# SimpleFOC.net
KiCad netlist of a schematic drawn in Altium Designer
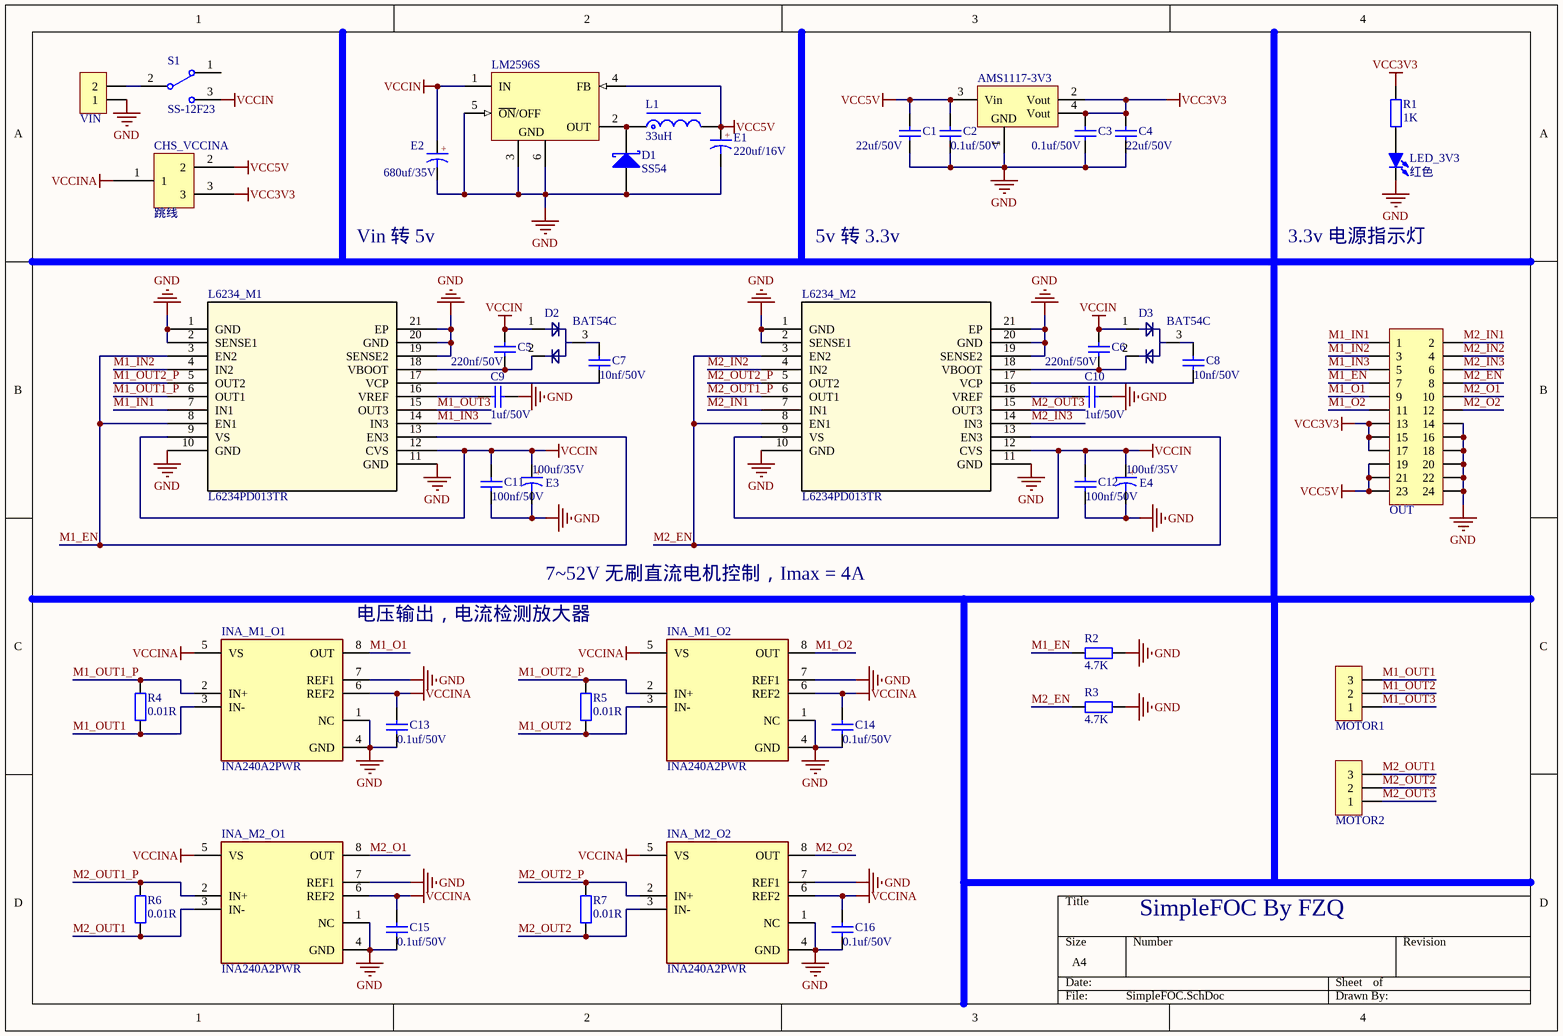
[diagram p0: SimpleFOC.SchDoc]

(export (version "E")
  (design (tool "Eeschema 10.0.6"))
  (components
    (comp (ref "AMS1117-3V3")
      (value "AMS1117-3V3")
      (footprint "SOT223_L")
      (description "三端稳压芯片")
      (libsource (lib "1.1 - 电源类芯片") (part "AMS1117"))
    )
    (comp (ref "C1")
      (value "22uf/50V")
      (footprint "C0603_L")
      (description "贴片电容")
      (libsource (lib "0.1 - 电阻-电容-电感-电位器") (part "C"))
    )
    (comp (ref "C2")
      (value "0.1uf/50V")
      (footprint "C0603_L")
      (description "贴片电容")
      (libsource (lib "0.1 - 电阻-电容-电感-电位器") (part "C"))
    )
    (comp (ref "C3")
      (value "0.1uf/50V")
      (footprint "C0603_L")
      (description "贴片电容")
      (libsource (lib "0.1 - 电阻-电容-电感-电位器") (part "C"))
    )
    (comp (ref "C4")
      (value "22uf/50V")
      (footprint "C0603_L")
      (description "贴片电容")
      (libsource (lib "0.1 - 电阻-电容-电感-电位器") (part "C"))
    )
    (comp (ref "C5")
      (value "220nf/50V")
      (footprint "C0603_L")
      (description "贴片电容")
      (libsource (lib "0.1 - 电阻-电容-电感-电位器") (part "C"))
    )
    (comp (ref "C6")
      (value "220nf/50V")
      (footprint "C0603_L")
      (description "贴片电容")
      (libsource (lib "0.1 - 电阻-电容-电感-电位器") (part "C"))
    )
    (comp (ref "C7")
      (value "10nf/50V")
      (footprint "C0603_L")
      (description "贴片电容")
      (libsource (lib "0.1 - 电阻-电容-电感-电位器") (part "C"))
    )
    (comp (ref "C8")
      (value "10nf/50V")
      (footprint "C0603_L")
      (description "贴片电容")
      (libsource (lib "0.1 - 电阻-电容-电感-电位器") (part "C"))
    )
    (comp (ref "C9")
      (value "1uf/50V")
      (footprint "C0603_L")
      (description "贴片电容")
      (libsource (lib "0.1 - 电阻-电容-电感-电位器") (part "C"))
    )
    (comp (ref "C10")
      (value "1uf/50V")
      (footprint "C0603_L")
      (description "贴片电容")
      (libsource (lib "0.1 - 电阻-电容-电感-电位器") (part "C"))
    )
    (comp (ref "C11")
      (value "100nf/50V")
      (footprint "C0603_L")
      (description "贴片电容")
      (libsource (lib "0.1 - 电阻-电容-电感-电位器") (part "C"))
    )
    (comp (ref "C12")
      (value "100nf/50V")
      (footprint "C0603_L")
      (description "贴片电容")
      (libsource (lib "0.1 - 电阻-电容-电感-电位器") (part "C"))
    )
    (comp (ref "C13")
      (value "0.1uf/50V")
      (footprint "C0603_L")
      (description "贴片电容")
      (libsource (lib "0.1 - 电阻-电容-电感-电位器") (part "C"))
    )
    (comp (ref "C14")
      (value "0.1uf/50V")
      (footprint "C0603_L")
      (description "贴片电容")
      (libsource (lib "0.1 - 电阻-电容-电感-电位器") (part "C"))
    )
    (comp (ref "C15")
      (value "0.1uf/50V")
      (footprint "C0603_L")
      (description "贴片电容")
      (libsource (lib "0.1 - 电阻-电容-电感-电位器") (part "C"))
    )
    (comp (ref "C16")
      (value "0.1uf/50V")
      (footprint "C0603_L")
      (description "贴片电容")
      (libsource (lib "0.1 - 电阻-电容-电感-电位器") (part "C"))
    )
    (comp (ref "CHS_VCCINA") (value "跳线") (footprint "0603") (libsource (lib "SimpleFOC") (part "跳线")))
    (comp (ref "D1")
      (value "SS54")
      (footprint "SMA")
      (description "肖特基二极管(5A/40V)")
      (libsource (lib "0.2 - 二极管-TVS-整流桥") (part "SS14"))
    )
    (comp (ref "D2")
      (value "BAT54C")
      (footprint "SOT23-3N")
      (description "两路肖特基二极管")
      (libsource (lib "SimpleFOC") (part "LBAT54SLT1G"))
    )
    (comp (ref "D3")
      (value "BAT54C")
      (footprint "SOT23-3N")
      (description "两路肖特基二极管")
      (libsource (lib "SimpleFOC") (part "LBAT54SLT1G"))
    )
    (comp (ref "E1")
      (value "220uf/16V")
      (footprint "CE D(6.3*7.7)")
      (description "贴片电解电容")
      (libsource (lib "0.1 - 电阻-电容-电感-电位器") (part "CE_SMD"))
    )
    (comp (ref "E2")
      (value "680uf/35V")
      (footprint "CE G(12.5*13.5)")
      (description "贴片电解电容")
      (libsource (lib "0.1 - 电阻-电容-电感-电位器") (part "CE_SMD"))
    )
    (comp (ref "E3")
      (value "100uf/35V")
      (footprint "CE D(6.3*7.7)")
      (description "贴片电解电容")
      (libsource (lib "0.1 - 电阻-电容-电感-电位器") (part "CE_SMD"))
    )
    (comp (ref "E4")
      (value "100uf/35V")
      (footprint "CE D(6.3*7.7)")
      (description "贴片电解电容")
      (libsource (lib "0.1 - 电阻-电容-电感-电位器") (part "CE_SMD"))
    )
    (comp (ref "INA_M1_O1")
      (value "INA240A2PWR")
      (footprint "INA240A2PWR")
      (description "IC AMP CURRENT SENSE 8-TSSOP")
      (fields
        (field (name "OCTOPART") "https://octopart.com/ina240a2pwr-texas+instruments-75431049")
        (field (name "MANUFACTURER") "Texas Instruments")
      )
      (libsource (lib "SimpleFOC") (part "INA240A2PWR"))
    )
    (comp (ref "INA_M1_O2")
      (value "INA240A2PWR")
      (footprint "INA240A2PWR")
      (description "IC AMP CURRENT SENSE 8-TSSOP")
      (fields
        (field (name "OCTOPART") "https://octopart.com/ina240a2pwr-texas+instruments-75431049")
        (field (name "MANUFACTURER") "Texas Instruments")
      )
      (libsource (lib "SimpleFOC") (part "INA240A2PWR"))
    )
    (comp (ref "INA_M2_O1")
      (value "INA240A2PWR")
      (footprint "INA240A2PWR")
      (description "IC AMP CURRENT SENSE 8-TSSOP")
      (fields
        (field (name "OCTOPART") "https://octopart.com/ina240a2pwr-texas+instruments-75431049")
        (field (name "MANUFACTURER") "Texas Instruments")
      )
      (libsource (lib "SimpleFOC") (part "INA240A2PWR"))
    )
    (comp (ref "INA_M2_O2")
      (value "INA240A2PWR")
      (footprint "INA240A2PWR")
      (description "IC AMP CURRENT SENSE 8-TSSOP")
      (fields
        (field (name "OCTOPART") "https://octopart.com/ina240a2pwr-texas+instruments-75431049")
        (field (name "MANUFACTURER") "Texas Instruments")
      )
      (libsource (lib "SimpleFOC") (part "INA240A2PWR"))
    )
    (comp (ref "L1")
      (value "33uH")
      (footprint "CDRH74")
      (description "CDRH功率屏蔽电感")
      (libsource (lib "0.1 - 电阻-电容-电感-电位器") (part "L-CDRH"))
    )
    (comp (ref "L6234_M1")
      (value "L6234PD013TR")
      (footprint "SOIC127P1420X360-21N")
      (description "No Description Available")
      (fields (field (name "COPYRIGHT") "Copyright (C) 2021 Accelerated Designs. All rights reserved"))
      (libsource (lib "SimpleFOC") (part "L6234PD013TR"))
    )
    (comp (ref "L6234_M2")
      (value "L6234PD013TR")
      (footprint "SOIC127P1420X360-21N")
      (description "No Description Available")
      (fields (field (name "COPYRIGHT") "Copyright (C) 2021 Accelerated Designs. All rights reserved"))
      (libsource (lib "SimpleFOC") (part "L6234PD013TR"))
    )
    (comp (ref "LED_3V3")
      (value "红色")
      (footprint "LED0603_R")
      (description "贴片LED")
      (libsource (lib "0.3 - LED发光二极管") (part "LED-SMD"))
    )
    (comp (ref "LM2596S")
      (value "LM2596S")
      (footprint "TO263-5A")
      (description "3A DC-DC降压芯片")
      (libsource (lib "1.1 - 电源类芯片") (part "LM2596S"))
    )
    (comp (ref "MOTOR1")
      (value "HDR-1X3")
      (footprint "KF301-5.0-3P")
      (description "3P接插件")
      (libsource (lib "6.0 - 接插件-脚距5.0") (part "Header 3"))
    )
    (comp (ref "MOTOR2")
      (value "HDR-1X3")
      (footprint "KF301-5.0-3P")
      (description "3P接插件")
      (libsource (lib "6.0 - 接插件-脚距5.0") (part "Header 3"))
    )
    (comp (ref "OUT")
      (value "Header 2X11")
      (footprint "HDR2.54-LI-2x12P")
      (description "12*2P接插件")
      (libsource (lib "5.4 - 接插件-脚距2.54 (100mil) ") (part "Header 12X2"))
    )
    (comp (ref "R1")
      (value "1K")
      (footprint "R0603_L")
      (description "贴片电阻")
      (libsource (lib "0.1 - 电阻-电容-电感-电位器") (part "R"))
    )
    (comp (ref "R2")
      (value "4.7K")
      (footprint "R0603_L")
      (description "贴片电阻")
      (libsource (lib "0.1 - 电阻-电容-电感-电位器") (part "R"))
    )
    (comp (ref "R3")
      (value "4.7K")
      (footprint "R0603_L")
      (description "贴片电阻")
      (libsource (lib "0.1 - 电阻-电容-电感-电位器") (part "R"))
    )
    (comp (ref "R4")
      (value "0.01R")
      (footprint "R0805_L")
      (description "贴片电阻")
      (libsource (lib "0.1 - 电阻-电容-电感-电位器") (part "R"))
    )
    (comp (ref "R5")
      (value "0.01R")
      (footprint "R0805_L")
      (description "贴片电阻")
      (libsource (lib "0.1 - 电阻-电容-电感-电位器") (part "R"))
    )
    (comp (ref "R6")
      (value "0.01R")
      (footprint "R0805_L")
      (description "贴片电阻")
      (libsource (lib "0.1 - 电阻-电容-电感-电位器") (part "R"))
    )
    (comp (ref "R7")
      (value "0.01R")
      (footprint "R0805_L")
      (description "贴片电阻")
      (libsource (lib "0.1 - 电阻-电容-电感-电位器") (part "R"))
    )
    (comp (ref "S1")
      (value "SS-12F23")
      (footprint "SS-12D10")
      (description "1路波动开关")
      (libsource (lib "0.7 - 常用按键-开关-蜂鸣器-电池-测试点") (part "SSW-1P"))
    )
    (comp (ref "VIN")
      (value "HDR-1X2")
      (footprint "KF301-5.0-2P")
      (description "2P接插件")
      (libsource (lib "6.0 - 接插件-脚距5.0") (part "Header 2"))
    )
  )
  (nets
    (net (code "1") (name "/M1_EN") (class "Default")
      (node (ref "L6234_M1") (pin "13") (pinfunction "EN3_13") (pintype "passive"))
      (node (ref "L6234_M1") (pin "3") (pinfunction "EN2_3") (pintype "passive"))
      (node (ref "L6234_M1") (pin "8") (pinfunction "EN1_8") (pintype "passive"))
      (node (ref "OUT") (pin "7") (pinfunction "7_7") (pintype "passive"))
      (node (ref "R2") (pin "1") (pinfunction "1_1") (pintype "passive"))
    )
    (net (code "2") (name "/M1_IN1") (class "Default")
      (node (ref "L6234_M1") (pin "7") (pinfunction "IN1_7") (pintype "passive"))
      (node (ref "OUT") (pin "1") (pinfunction "1_1") (pintype "passive"))
    )
    (net (code "3") (name "/M1_IN2") (class "Default")
      (node (ref "L6234_M1") (pin "4") (pinfunction "IN2_4") (pintype "passive"))
      (node (ref "OUT") (pin "3") (pinfunction "3_3") (pintype "passive"))
    )
    (net (code "4") (name "/M1_IN3") (class "Default")
      (node (ref "L6234_M1") (pin "14") (pinfunction "IN3_14") (pintype "passive"))
      (node (ref "OUT") (pin "5") (pinfunction "5_5") (pintype "passive"))
    )
    (net (code "5") (name "/M1_O1") (class "Default")
      (node (ref "INA_M1_O1") (pin "8") (pinfunction "OUT_8") (pintype "passive"))
      (node (ref "OUT") (pin "9") (pinfunction "9_9") (pintype "passive"))
    )
    (net (code "6") (name "/M1_O2") (class "Default")
      (node (ref "INA_M1_O2") (pin "8") (pinfunction "OUT_8") (pintype "passive"))
      (node (ref "OUT") (pin "11") (pinfunction "11_11") (pintype "passive"))
    )
    (net (code "7") (name "/M1_OUT1") (class "Default")
      (node (ref "INA_M1_O1") (pin "3") (pinfunction "IN-_3") (pintype "tri_state"))
      (node (ref "MOTOR1") (pin "3") (pinfunction "3_3") (pintype "passive"))
      (node (ref "R4") (pin "2") (pinfunction "2_2") (pintype "passive"))
    )
    (net (code "8") (name "/M1_OUT1_P") (class "Default")
      (node (ref "INA_M1_O1") (pin "2") (pinfunction "IN+_2") (pintype "tri_state"))
      (node (ref "L6234_M1") (pin "6") (pinfunction "OUT1_6") (pintype "passive"))
      (node (ref "R4") (pin "1") (pinfunction "1_1") (pintype "passive"))
    )
    (net (code "9") (name "/M1_OUT2") (class "Default")
      (node (ref "INA_M1_O2") (pin "3") (pinfunction "IN-_3") (pintype "tri_state"))
      (node (ref "MOTOR1") (pin "2") (pinfunction "2_2") (pintype "passive"))
      (node (ref "R5") (pin "2") (pinfunction "2_2") (pintype "passive"))
    )
    (net (code "10") (name "/M1_OUT2_P") (class "Default")
      (node (ref "INA_M1_O2") (pin "2") (pinfunction "IN+_2") (pintype "tri_state"))
      (node (ref "L6234_M1") (pin "5") (pinfunction "OUT2_5") (pintype "passive"))
      (node (ref "R5") (pin "1") (pinfunction "1_1") (pintype "passive"))
    )
    (net (code "11") (name "/M1_OUT3") (class "Default")
      (node (ref "L6234_M1") (pin "15") (pinfunction "OUT3_15") (pintype "passive"))
      (node (ref "MOTOR1") (pin "1") (pinfunction "1_1") (pintype "passive"))
    )
    (net (code "12") (name "/M2_EN") (class "Default")
      (node (ref "L6234_M2") (pin "13") (pinfunction "EN3_13") (pintype "passive"))
      (node (ref "L6234_M2") (pin "3") (pinfunction "EN2_3") (pintype "passive"))
      (node (ref "L6234_M2") (pin "8") (pinfunction "EN1_8") (pintype "passive"))
      (node (ref "OUT") (pin "8") (pinfunction "8_8") (pintype "passive"))
      (node (ref "R3") (pin "1") (pinfunction "1_1") (pintype "passive"))
    )
    (net (code "13") (name "/M2_IN1") (class "Default")
      (node (ref "L6234_M2") (pin "7") (pinfunction "IN1_7") (pintype "passive"))
      (node (ref "OUT") (pin "2") (pinfunction "2_2") (pintype "passive"))
    )
    (net (code "14") (name "/M2_IN2") (class "Default")
      (node (ref "L6234_M2") (pin "4") (pinfunction "IN2_4") (pintype "passive"))
      (node (ref "OUT") (pin "4") (pinfunction "4_4") (pintype "passive"))
    )
    (net (code "15") (name "/M2_IN3") (class "Default")
      (node (ref "L6234_M2") (pin "14") (pinfunction "IN3_14") (pintype "passive"))
      (node (ref "OUT") (pin "6") (pinfunction "6_6") (pintype "passive"))
    )
    (net (code "16") (name "/M2_O1") (class "Default")
      (node (ref "INA_M2_O1") (pin "8") (pinfunction "OUT_8") (pintype "passive"))
      (node (ref "OUT") (pin "10") (pinfunction "10_10") (pintype "passive"))
    )
    (net (code "17") (name "/M2_O2") (class "Default")
      (node (ref "INA_M2_O2") (pin "8") (pinfunction "OUT_8") (pintype "passive"))
      (node (ref "OUT") (pin "12") (pinfunction "12_12") (pintype "passive"))
    )
    (net (code "18") (name "/M2_OUT1") (class "Default")
      (node (ref "INA_M2_O1") (pin "3") (pinfunction "IN-_3") (pintype "tri_state"))
      (node (ref "MOTOR2") (pin "3") (pinfunction "3_3") (pintype "passive"))
      (node (ref "R6") (pin "2") (pinfunction "2_2") (pintype "passive"))
    )
    (net (code "19") (name "/M2_OUT1_P") (class "Default")
      (node (ref "INA_M2_O1") (pin "2") (pinfunction "IN+_2") (pintype "tri_state"))
      (node (ref "L6234_M2") (pin "6") (pinfunction "OUT1_6") (pintype "passive"))
      (node (ref "R6") (pin "1") (pinfunction "1_1") (pintype "passive"))
    )
    (net (code "20") (name "/M2_OUT2") (class "Default")
      (node (ref "INA_M2_O2") (pin "3") (pinfunction "IN-_3") (pintype "tri_state"))
      (node (ref "MOTOR2") (pin "2") (pinfunction "2_2") (pintype "passive"))
      (node (ref "R7") (pin "2") (pinfunction "2_2") (pintype "passive"))
    )
    (net (code "21") (name "/M2_OUT2_P") (class "Default")
      (node (ref "INA_M2_O2") (pin "2") (pinfunction "IN+_2") (pintype "tri_state"))
      (node (ref "L6234_M2") (pin "5") (pinfunction "OUT2_5") (pintype "passive"))
      (node (ref "R7") (pin "1") (pinfunction "1_1") (pintype "passive"))
    )
    (net (code "22") (name "/M2_OUT3") (class "Default")
      (node (ref "L6234_M2") (pin "15") (pinfunction "OUT3_15") (pintype "passive"))
      (node (ref "MOTOR2") (pin "1") (pinfunction "1_1") (pintype "passive"))
    )
    (net (code "23") (name "GND") (class "Default")
      (node (ref "AMS1117-3V3") (pin "1") (pinfunction "GND_1") (pintype "passive"))
      (node (ref "C1") (pin "1") (pinfunction "1_1") (pintype "passive"))
      (node (ref "C10") (pin "1") (pinfunction "1_1") (pintype "passive"))
      (node (ref "C11") (pin "1") (pinfunction "1_1") (pintype "passive"))
      (node (ref "C12") (pin "1") (pinfunction "1_1") (pintype "passive"))
      (node (ref "C13") (pin "1") (pinfunction "1_1") (pintype "passive"))
      (node (ref "C14") (pin "1") (pinfunction "1_1") (pintype "passive"))
      (node (ref "C15") (pin "1") (pinfunction "1_1") (pintype "passive"))
      (node (ref "C16") (pin "1") (pinfunction "1_1") (pintype "passive"))
      (node (ref "C2") (pin "1") (pinfunction "1_1") (pintype "passive"))
      (node (ref "C3") (pin "1") (pinfunction "1_1") (pintype "passive"))
      (node (ref "C4") (pin "1") (pinfunction "1_1") (pintype "passive"))
      (node (ref "C9") (pin "1") (pinfunction "1_1") (pintype "passive"))
      (node (ref "D1") (pin "1") (pinfunction "A_1") (pintype "passive"))
      (node (ref "E1") (pin "2") (pinfunction "2_2") (pintype "passive"))
      (node (ref "E2") (pin "2") (pinfunction "2_2") (pintype "passive"))
      (node (ref "E3") (pin "2") (pinfunction "2_2") (pintype "passive"))
      (node (ref "E4") (pin "2") (pinfunction "2_2") (pintype "passive"))
      (node (ref "INA_M1_O1") (pin "1") (pinfunction "NC_1") (pintype "passive"))
      (node (ref "INA_M1_O1") (pin "4") (pinfunction "GND_4") (pintype "power_in"))
      (node (ref "INA_M1_O1") (pin "7") (pinfunction "REF1_7") (pintype "passive"))
      (node (ref "INA_M1_O2") (pin "1") (pinfunction "NC_1") (pintype "passive"))
      (node (ref "INA_M1_O2") (pin "4") (pinfunction "GND_4") (pintype "power_in"))
      (node (ref "INA_M1_O2") (pin "7") (pinfunction "REF1_7") (pintype "passive"))
      (node (ref "INA_M2_O1") (pin "1") (pinfunction "NC_1") (pintype "passive"))
      (node (ref "INA_M2_O1") (pin "4") (pinfunction "GND_4") (pintype "power_in"))
      (node (ref "INA_M2_O1") (pin "7") (pinfunction "REF1_7") (pintype "passive"))
      (node (ref "INA_M2_O2") (pin "1") (pinfunction "NC_1") (pintype "passive"))
      (node (ref "INA_M2_O2") (pin "4") (pinfunction "GND_4") (pintype "power_in"))
      (node (ref "INA_M2_O2") (pin "7") (pinfunction "REF1_7") (pintype "passive"))
      (node (ref "L6234_M1") (pin "1") (pinfunction "GND_1") (pintype "power_in"))
      (node (ref "L6234_M1") (pin "10") (pinfunction "GND_10") (pintype "power_in"))
      (node (ref "L6234_M1") (pin "11") (pinfunction "GND_11") (pintype "power_in"))
      (node (ref "L6234_M1") (pin "19") (pinfunction "SENSE2_19") (pintype "passive"))
      (node (ref "L6234_M1") (pin "2") (pinfunction "SENSE1_2") (pintype "passive"))
      (node (ref "L6234_M1") (pin "20") (pinfunction "GND_20") (pintype "power_in"))
      (node (ref "L6234_M1") (pin "21") (pinfunction "EP_21") (pintype "passive"))
      (node (ref "L6234_M2") (pin "1") (pinfunction "GND_1") (pintype "power_in"))
      (node (ref "L6234_M2") (pin "10") (pinfunction "GND_10") (pintype "power_in"))
      (node (ref "L6234_M2") (pin "11") (pinfunction "GND_11") (pintype "power_in"))
      (node (ref "L6234_M2") (pin "19") (pinfunction "SENSE2_19") (pintype "passive"))
      (node (ref "L6234_M2") (pin "2") (pinfunction "SENSE1_2") (pintype "passive"))
      (node (ref "L6234_M2") (pin "20") (pinfunction "GND_20") (pintype "power_in"))
      (node (ref "L6234_M2") (pin "21") (pinfunction "EP_21") (pintype "passive"))
      (node (ref "LED_3V3") (pin "2") (pinfunction "K_2") (pintype "passive"))
      (node (ref "LM2596S") (pin "3") (pinfunction "GND_3") (pintype "power_in"))
      (node (ref "LM2596S") (pin "5") (pinfunction "~{ON}/OFF_5") (pintype "input"))
      (node (ref "LM2596S") (pin "6") (pinfunction "GND_6") (pintype "power_in"))
      (node (ref "OUT") (pin "14") (pinfunction "14_14") (pintype "passive"))
      (node (ref "OUT") (pin "16") (pinfunction "16_16") (pintype "passive"))
      (node (ref "OUT") (pin "18") (pinfunction "18_18") (pintype "passive"))
      (node (ref "OUT") (pin "20") (pinfunction "20_20") (pintype "passive"))
      (node (ref "OUT") (pin "22") (pinfunction "22_22") (pintype "passive"))
      (node (ref "OUT") (pin "24") (pinfunction "24_24") (pintype "passive"))
      (node (ref "R2") (pin "2") (pinfunction "2_2") (pintype "passive"))
      (node (ref "R3") (pin "2") (pinfunction "2_2") (pintype "passive"))
      (node (ref "VIN") (pin "1") (pinfunction "1_1") (pintype "passive"))
    )
    (net (code "24") (name "Net-(C7-Pad2)") (class "Default")
      (node (ref "C7") (pin "2") (pinfunction "2_2") (pintype "passive"))
      (node (ref "D2") (pin "3") (pinfunction "3_3") (pintype "passive"))
    )
    (net (code "25") (name "Net-(C8-Pad2)") (class "Default")
      (node (ref "C8") (pin "2") (pinfunction "2_2") (pintype "passive"))
      (node (ref "D3") (pin "3") (pinfunction "3_3") (pintype "passive"))
    )
    (net (code "26") (name "Net-(D1-K)") (class "Default")
      (node (ref "D1") (pin "2") (pinfunction "K_2") (pintype "passive"))
      (node (ref "L1") (pin "1") (pinfunction "1_1") (pintype "passive"))
      (node (ref "LM2596S") (pin "2") (pinfunction "OUT_2") (pintype "power_in"))
    )
    (net (code "27") (name "Net-(L6234_M1-VBOOT)") (class "Default")
      (node (ref "C5") (pin "1") (pinfunction "1_1") (pintype "passive"))
      (node (ref "D2") (pin "2") (pinfunction "2_2") (pintype "passive"))
      (node (ref "L6234_M1") (pin "18") (pinfunction "VBOOT_18") (pintype "power_in"))
    )
    (net (code "28") (name "Net-(L6234_M1-VCP)") (class "Default")
      (node (ref "C7") (pin "1") (pinfunction "1_1") (pintype "passive"))
      (node (ref "L6234_M1") (pin "17") (pinfunction "VCP_17") (pintype "power_in"))
    )
    (net (code "29") (name "Net-(L6234_M1-VREF)") (class "Default")
      (node (ref "C9") (pin "2") (pinfunction "2_2") (pintype "passive"))
      (node (ref "L6234_M1") (pin "16") (pinfunction "VREF_16") (pintype "power_in"))
    )
    (net (code "30") (name "Net-(L6234_M2-VBOOT)") (class "Default")
      (node (ref "C6") (pin "1") (pinfunction "1_1") (pintype "passive"))
      (node (ref "D3") (pin "2") (pinfunction "2_2") (pintype "passive"))
      (node (ref "L6234_M2") (pin "18") (pinfunction "VBOOT_18") (pintype "power_in"))
    )
    (net (code "31") (name "Net-(L6234_M2-VCP)") (class "Default")
      (node (ref "C8") (pin "1") (pinfunction "1_1") (pintype "passive"))
      (node (ref "L6234_M2") (pin "17") (pinfunction "VCP_17") (pintype "power_in"))
    )
    (net (code "32") (name "Net-(L6234_M2-VREF)") (class "Default")
      (node (ref "C10") (pin "2") (pinfunction "2_2") (pintype "passive"))
      (node (ref "L6234_M2") (pin "16") (pinfunction "VREF_16") (pintype "power_in"))
    )
    (net (code "33") (name "Net-(LED_3V3-A)") (class "Default")
      (node (ref "LED_3V3") (pin "1") (pinfunction "A_1") (pintype "passive"))
      (node (ref "R1") (pin "2") (pinfunction "2_2") (pintype "passive"))
    )
    (net (code "34") (name "Net-(S1-Pad2)") (class "Default")
      (node (ref "S1") (pin "2") (pinfunction "2_2") (pintype "passive"))
      (node (ref "VIN") (pin "2") (pinfunction "2_2") (pintype "passive"))
    )
    (net (code "35") (name "VCC3V3") (class "Default")
      (node (ref "AMS1117-3V3") (pin "2") (pinfunction "Vout_2") (pintype "passive"))
      (node (ref "AMS1117-3V3") (pin "4") (pinfunction "Vout_4") (pintype "passive"))
      (node (ref "C3") (pin "2") (pinfunction "2_2") (pintype "passive"))
      (node (ref "C4") (pin "2") (pinfunction "2_2") (pintype "passive"))
      (node (ref "CHS_VCCINA") (pin "3") (pinfunction "3_3") (pintype "passive"))
      (node (ref "OUT") (pin "13") (pinfunction "13_13") (pintype "passive"))
      (node (ref "OUT") (pin "15") (pinfunction "15_15") (pintype "passive"))
      (node (ref "OUT") (pin "17") (pinfunction "17_17") (pintype "passive"))
      (node (ref "R1") (pin "1") (pinfunction "1_1") (pintype "passive"))
    )
    (net (code "36") (name "VCC5V") (class "Default")
      (node (ref "AMS1117-3V3") (pin "3") (pinfunction "Vin_3") (pintype "passive"))
      (node (ref "C1") (pin "2") (pinfunction "2_2") (pintype "passive"))
      (node (ref "C2") (pin "2") (pinfunction "2_2") (pintype "passive"))
      (node (ref "CHS_VCCINA") (pin "2") (pinfunction "2_2") (pintype "passive"))
      (node (ref "E1") (pin "1") (pinfunction "1_1") (pintype "passive"))
      (node (ref "L1") (pin "2") (pinfunction "2_2") (pintype "passive"))
      (node (ref "LM2596S") (pin "4") (pinfunction "FB_4") (pintype "input"))
      (node (ref "OUT") (pin "19") (pinfunction "19_19") (pintype "passive"))
      (node (ref "OUT") (pin "21") (pinfunction "21_21") (pintype "passive"))
      (node (ref "OUT") (pin "23") (pinfunction "23_23") (pintype "passive"))
    )
    (net (code "37") (name "VCCIN") (class "Default")
      (node (ref "C11") (pin "2") (pinfunction "2_2") (pintype "passive"))
      (node (ref "C12") (pin "2") (pinfunction "2_2") (pintype "passive"))
      (node (ref "C5") (pin "2") (pinfunction "2_2") (pintype "passive"))
      (node (ref "C6") (pin "2") (pinfunction "2_2") (pintype "passive"))
      (node (ref "D2") (pin "1") (pinfunction "1_1") (pintype "passive"))
      (node (ref "D3") (pin "1") (pinfunction "1_1") (pintype "passive"))
      (node (ref "E2") (pin "1") (pinfunction "1_1") (pintype "passive"))
      (node (ref "E3") (pin "1") (pinfunction "1_1") (pintype "passive"))
      (node (ref "E4") (pin "1") (pinfunction "1_1") (pintype "passive"))
      (node (ref "L6234_M1") (pin "12") (pinfunction "CVS_12") (pintype "passive"))
      (node (ref "L6234_M1") (pin "9") (pinfunction "VS_9") (pintype "power_in"))
      (node (ref "L6234_M2") (pin "12") (pinfunction "CVS_12") (pintype "passive"))
      (node (ref "L6234_M2") (pin "9") (pinfunction "VS_9") (pintype "power_in"))
      (node (ref "LM2596S") (pin "1") (pinfunction "IN_1") (pintype "power_in"))
      (node (ref "S1") (pin "3") (pinfunction "3_3") (pintype "passive"))
    )
    (net (code "38") (name "VCCINA") (class "Default")
      (node (ref "C13") (pin "2") (pinfunction "2_2") (pintype "passive"))
      (node (ref "C14") (pin "2") (pinfunction "2_2") (pintype "passive"))
      (node (ref "C15") (pin "2") (pinfunction "2_2") (pintype "passive"))
      (node (ref "C16") (pin "2") (pinfunction "2_2") (pintype "passive"))
      (node (ref "CHS_VCCINA") (pin "1") (pinfunction "1_1") (pintype "passive"))
      (node (ref "INA_M1_O1") (pin "5") (pinfunction "VS_5") (pintype "power_in"))
      (node (ref "INA_M1_O1") (pin "6") (pinfunction "REF2_6") (pintype "passive"))
      (node (ref "INA_M1_O2") (pin "5") (pinfunction "VS_5") (pintype "power_in"))
      (node (ref "INA_M1_O2") (pin "6") (pinfunction "REF2_6") (pintype "passive"))
      (node (ref "INA_M2_O1") (pin "5") (pinfunction "VS_5") (pintype "power_in"))
      (node (ref "INA_M2_O1") (pin "6") (pinfunction "REF2_6") (pintype "passive"))
      (node (ref "INA_M2_O2") (pin "5") (pinfunction "VS_5") (pintype "power_in"))
      (node (ref "INA_M2_O2") (pin "6") (pinfunction "REF2_6") (pintype "passive"))
    )
    (net (code "39") (name "unconnected-(S1-Pad1)") (class "Default")
      (node (ref "S1") (pin "1") (pinfunction "1_1") (pintype "passive"))
    )
  )
)
